# CMC_NIBP.net
KiCad netlist of a schematic drawn in EAGLE
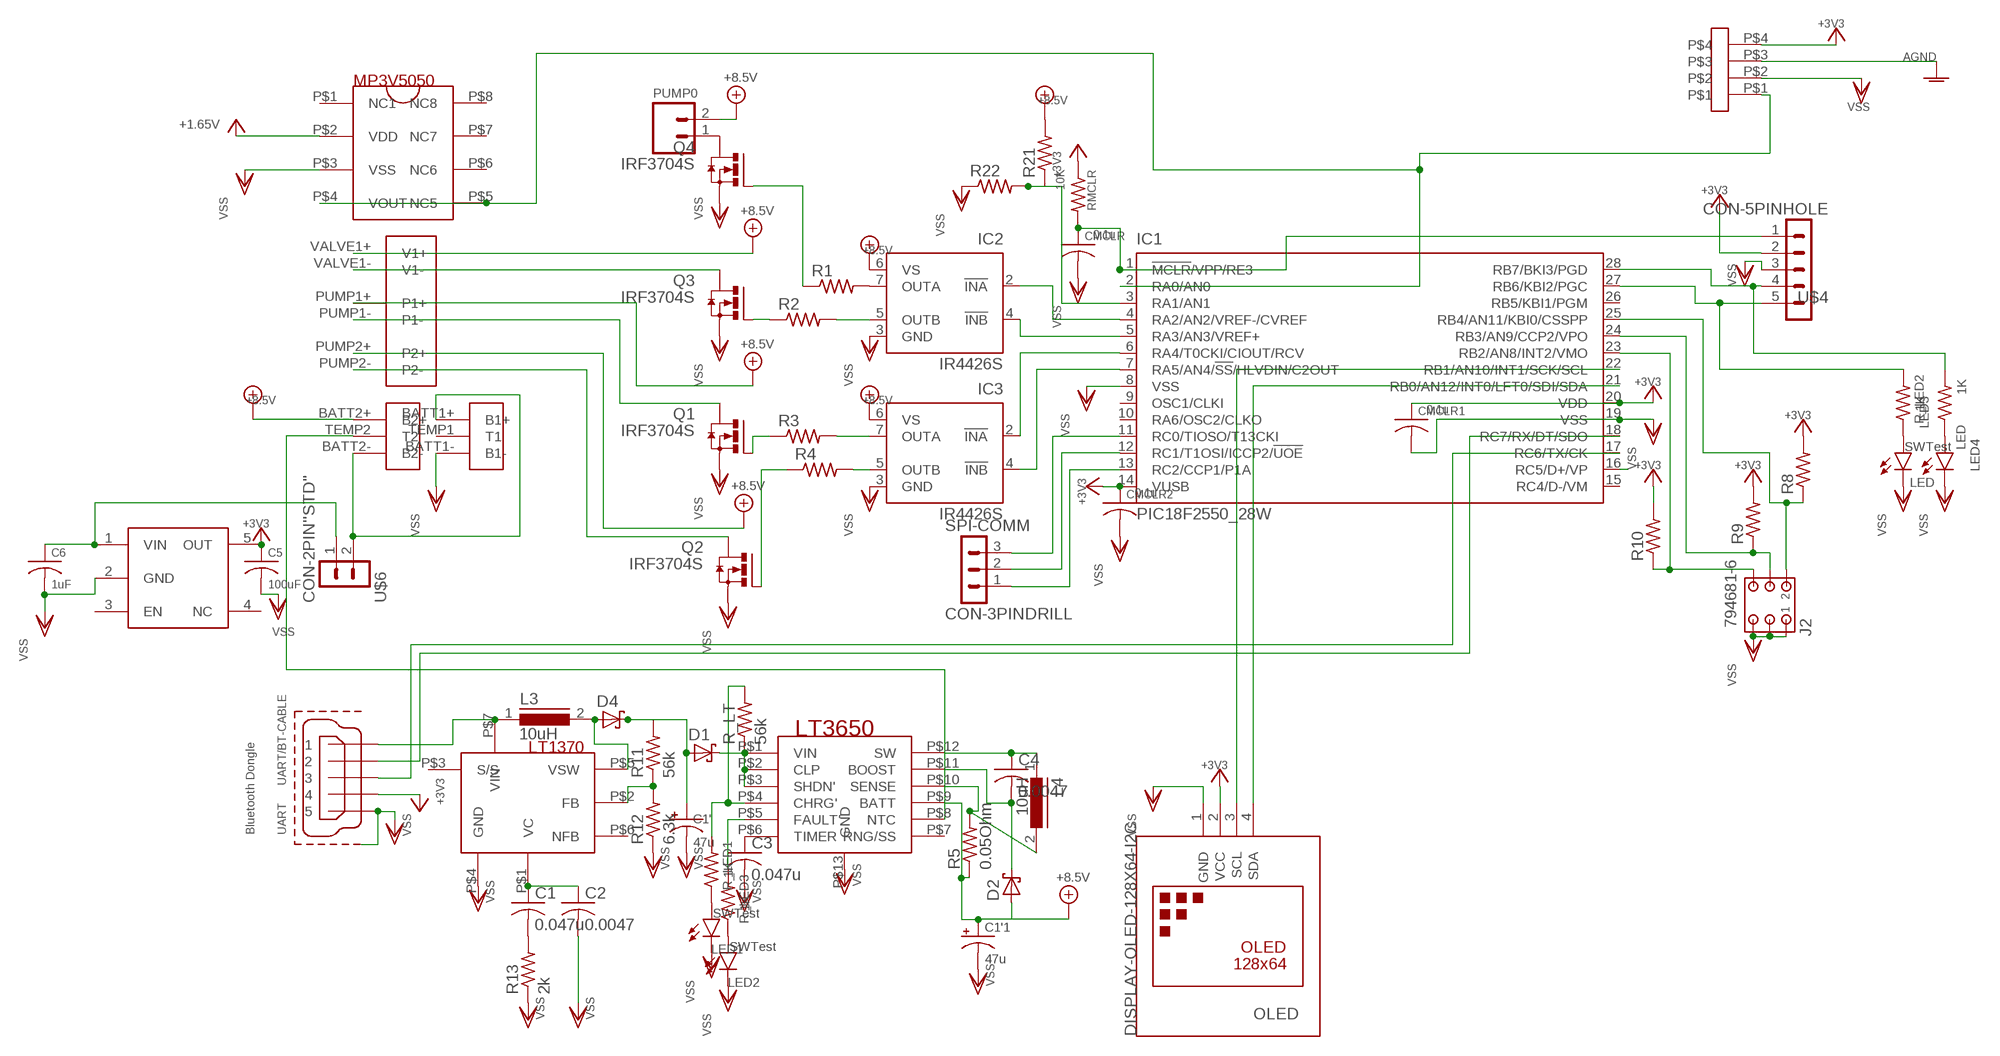
[diagram p0: schematic, sheet 1]

(export (version "E")
  (design (tool "Eeschema 10.0.6"))
  (components
    (comp (ref "C1")
      (value "0.047u")
      (footprint "eagle-import:C1206")
      (libsource (lib "eagle-import") (part "C-USC1206"))
    )
    (comp (ref "C1'")
      (value "47u")
      (footprint "eagle-import:E5-10,5")
      (libsource (lib "eagle-import") (part "CPOL-USE5-10.5"))
    )
    (comp (ref "C1'1")
      (value "47u")
      (footprint "eagle-import:E5-10,5")
      (libsource (lib "eagle-import") (part "CPOL-USE5-10.5"))
    )
    (comp (ref "C2")
      (value "0.0047")
      (footprint "eagle-import:C1206")
      (libsource (lib "eagle-import") (part "C-USC1206"))
    )
    (comp (ref "C3")
      (value "0.047u")
      (footprint "eagle-import:C1206")
      (libsource (lib "eagle-import") (part "C-USC1206"))
    )
    (comp (ref "C4")
      (value "0.0047")
      (footprint "eagle-import:C1206")
      (libsource (lib "eagle-import") (part "C-USC1206"))
    )
    (comp (ref "C5")
      (value "100uF")
      (footprint "eagle-import:C1210")
      (libsource (lib "eagle-import") (part "C-USC1210"))
    )
    (comp (ref "C6")
      (value "1uF")
      (footprint "eagle-import:C0603")
      (libsource (lib "eagle-import") (part "C-USC0603"))
    )
    (comp (ref "CMCLR")
      (value "0.1u")
      (footprint "eagle-import:C0603")
      (libsource (lib "eagle-import") (part "C-USC0603"))
    )
    (comp (ref "CMCLR1")
      (value "0.1u")
      (footprint "eagle-import:C0603")
      (libsource (lib "eagle-import") (part "C-USC0603"))
    )
    (comp (ref "CMCLR2")
      (value "0.1u")
      (footprint "eagle-import:C0603")
      (libsource (lib "eagle-import") (part "C-USC0603"))
    )
    (comp (ref "D1")
      (value "SCHOTTKY-DIODESMD")
      (footprint "eagle-import:SMB")
      (libsource (lib "eagle-import") (part "SCHOTTKY-DIODESMD"))
    )
    (comp (ref "D2")
      (value "SCHOTTKY-DIODESMD")
      (footprint "eagle-import:SMB")
      (libsource (lib "eagle-import") (part "SCHOTTKY-DIODESMD"))
    )
    (comp (ref "D4")
      (value "SCHOTTKY-DIODESMD")
      (footprint "eagle-import:SMB")
      (libsource (lib "eagle-import") (part "SCHOTTKY-DIODESMD"))
    )
    (comp (ref "IC-3.3VREG")
      (value "LDO-MIC5307")
      (footprint "eagle-import:SOT23-5")
      (libsource (lib "eagle-import") (part "LDO-MIC5307"))
    )
    (comp (ref "IC1")
      (value "PIC18F2550_28W")
      (footprint "eagle-import:SO28W")
      (fields (field (name "MF") "MICROCHIP") (field (name "MPN") "PIC18F2550-I/SO"))
      (libsource (lib "eagle-import") (part "PIC18F2_28W550"))
    )
    (comp (ref "IC2")
      (value "IR4426S")
      (footprint "eagle-import:SO08")
      (fields (field (name "MF") "INTERNATIONAL RECTIFIER(IR)"))
      (libsource (lib "eagle-import") (part "IR4426S"))
    )
    (comp (ref "IC3")
      (value "IR4426S")
      (footprint "eagle-import:SO08")
      (fields (field (name "MF") "INTERNATIONAL RECTIFIER(IR)"))
      (libsource (lib "eagle-import") (part "IR4426S"))
    )
    (comp (ref "J2")
      (value "794681-6")
      (footprint "eagle-import:794681-6")
      (libsource (lib "eagle-import") (part "794681-6"))
    )
    (comp (ref "L3")
      (value "10uH")
      (footprint "eagle-import:DR73")
      (libsource (lib "eagle-import") (part "DR73"))
    )
    (comp (ref "L4")
      (value "10uH")
      (footprint "eagle-import:DR73")
      (libsource (lib "eagle-import") (part "DR73"))
    )
    (comp (ref "LED")
      (value "SWTest")
      (footprint "eagle-import:LED3MM")
      (libsource (lib "eagle-import") (part "LED3MM"))
    )
    (comp (ref "LED1")
      (value "SWTest")
      (footprint "eagle-import:LED3MM")
      (libsource (lib "eagle-import") (part "LED3MM"))
    )
    (comp (ref "LED2")
      (value "SWTest")
      (footprint "eagle-import:LED3MM")
      (libsource (lib "eagle-import") (part "LED3MM"))
    )
    (comp (ref "LED3")
      (value "1K")
      (footprint "eagle-import:0204V")
      (libsource (lib "eagle-import") (part "R-US_0204/2V"))
    )
    (comp (ref "LED4")
      (value "LED")
      (footprint "eagle-import:LED3MM")
      (libsource (lib "eagle-import") (part "LED3MM"))
    )
    (comp (ref "OLED")
      (value "DISPLAY-OLED-128X64-I2C")
      (footprint "eagle-import:DISPLAY-OLED-128X64-I2C")
      (libsource (lib "eagle-import") (part "DISPLAY-OLED-128X64-I2C"))
    )
    (comp (ref "PUMP0")
      (value "Pump0")
      (footprint "eagle-import:02P")
      (libsource (lib "eagle-import") (part "M02"))
    )
    (comp (ref "Q1")
      (value "IRF3704S")
      (footprint "eagle-import:D2PACK")
      (libsource (lib "eagle-import") (part "IRF3704S"))
    )
    (comp (ref "Q2")
      (value "IRF3704S")
      (footprint "eagle-import:D2PACK")
      (libsource (lib "eagle-import") (part "IRF3704S"))
    )
    (comp (ref "Q3")
      (value "IRF3704S")
      (footprint "eagle-import:D2PACK")
      (libsource (lib "eagle-import") (part "IRF3704S"))
    )
    (comp (ref "Q4")
      (value "IRF3704S")
      (footprint "eagle-import:D2PACK")
      (libsource (lib "eagle-import") (part "IRF3704S"))
    )
    (comp (ref "R1")
      (value "R-US_M1206")
      (footprint "eagle-import:M1206")
      (libsource (lib "eagle-import") (part "R-US_M1206"))
    )
    (comp (ref "R2")
      (value "R-US_M1206")
      (footprint "eagle-import:M1206")
      (libsource (lib "eagle-import") (part "R-US_M1206"))
    )
    (comp (ref "R3")
      (value "R-US_M1206")
      (footprint "eagle-import:M1206")
      (libsource (lib "eagle-import") (part "R-US_M1206"))
    )
    (comp (ref "R4")
      (value "R-US_M1206")
      (footprint "eagle-import:M1206")
      (libsource (lib "eagle-import") (part "R-US_M1206"))
    )
    (comp (ref "R5")
      (value "0.05Ohm")
      (footprint "eagle-import:M1206")
      (libsource (lib "eagle-import") (part "R-US_M1206"))
    )
    (comp (ref "R8")
      (value "R-US_M1206")
      (footprint "eagle-import:M1206")
      (libsource (lib "eagle-import") (part "R-US_M1206"))
    )
    (comp (ref "R9")
      (value "R-US_M1206")
      (footprint "eagle-import:M1206")
      (libsource (lib "eagle-import") (part "R-US_M1206"))
    )
    (comp (ref "R10")
      (value "R-US_M1206")
      (footprint "eagle-import:M1206")
      (libsource (lib "eagle-import") (part "R-US_M1206"))
    )
    (comp (ref "R11")
      (value "56k")
      (footprint "eagle-import:M1206")
      (libsource (lib "eagle-import") (part "R-US_M1206"))
    )
    (comp (ref "R12")
      (value "6.3k")
      (footprint "eagle-import:M1206")
      (libsource (lib "eagle-import") (part "R-US_M1206"))
    )
    (comp (ref "R13")
      (value "2k")
      (footprint "eagle-import:M1206")
      (libsource (lib "eagle-import") (part "R-US_M1206"))
    )
    (comp (ref "R21")
      (value "R-US_M1206")
      (footprint "eagle-import:M1206")
      (libsource (lib "eagle-import") (part "R-US_M1206"))
    )
    (comp (ref "R22")
      (value "R-US_M1206")
      (footprint "eagle-import:M1206")
      (libsource (lib "eagle-import") (part "R-US_M1206"))
    )
    (comp (ref "RMCLR")
      (value "10K")
      (footprint "eagle-import:R0603")
      (libsource (lib "eagle-import") (part "R-US_R0603"))
    )
    (comp (ref "R_LED1")
      (value "1K")
      (footprint "eagle-import:0204V")
      (libsource (lib "eagle-import") (part "R-US_0204/2V"))
    )
    (comp (ref "R_LED2")
      (value "1K")
      (footprint "eagle-import:0204V")
      (libsource (lib "eagle-import") (part "R-US_0204/2V"))
    )
    (comp (ref "R_LED3")
      (value "1K")
      (footprint "eagle-import:0204V")
      (libsource (lib "eagle-import") (part "R-US_0204/2V"))
    )
    (comp (ref "R_LT")
      (value "56k")
      (footprint "eagle-import:M1206")
      (libsource (lib "eagle-import") (part "R-US_M1206"))
    )
    (comp (ref "SPI-COMM")
      (value "CON-3PINDRILL")
      (footprint "eagle-import:CON-3PIN")
      (libsource (lib "eagle-import") (part "CON-3PINDRILL"))
    )
    (comp (ref "U$1")
      (value "NIBP_PNEUMATICS")
      (footprint "eagle-import:NIBP_PNEUM")
      (libsource (lib "eagle-import") (part "NIBP_PNEUMATICS"))
    )
    (comp (ref "U$2")
      (value "LT1370")
      (footprint "eagle-import:DD-PACK-7LEAD")
      (libsource (lib "eagle-import") (part "LT1370"))
    )
    (comp (ref "U$3")
      (value "LT3650")
      (footprint "eagle-import:MSOP-12")
      (libsource (lib "eagle-import") (part "LT3650"))
    )
    (comp (ref "U$4")
      (value "CON-5PINHOLE")
      (footprint "eagle-import:CON-5PIN")
      (libsource (lib "eagle-import") (part "CON-5PINHOLE"))
    )
    (comp (ref "U$5")
      (value "CON-4PIN_SIL")
      (footprint "eagle-import:CONN-4PINSIL2")
      (libsource (lib "eagle-import") (part "CON-4PIN_SIL"))
    )
    (comp (ref "U$6")
      (value "CON-2PIN''STD\"")
      (footprint "eagle-import:CON-2PIN")
      (libsource (lib "eagle-import") (part "CON-2PIN''STD{dblquote}"))
    )
    (comp (ref "UART/BT-CABLE")
      (value "UART")
      (footprint "eagle-import:MICRO-USB1")
      (libsource (lib "eagle-import") (part "MICRO-USB1"))
    )
  )
  (nets
    (net (code "1") (name "+1.65V") (class "Default")
      (node (ref "C5") (pin "1") (pinfunction "1_1") (pintype "passive"))
      (node (ref "CMCLR1") (pin "1") (pinfunction "1_1") (pintype "passive"))
      (node (ref "CMCLR2") (pin "1") (pinfunction "1_1") (pintype "passive"))
      (node (ref "IC-3.3VREG") (pin "5") (pinfunction "OUT_5") (pintype "bidirectional"))
      (node (ref "IC1") (pin "14") (pinfunction "VUSB_14") (pintype "bidirectional"))
      (node (ref "IC1") (pin "20") (pinfunction "VDD_20") (pintype "power_in"))
      (node (ref "OLED") (pin "2") (pinfunction "VCC_2") (pintype "power_in"))
      (node (ref "R10") (pin "2") (pinfunction "2_2") (pintype "passive"))
      (node (ref "R8") (pin "2") (pinfunction "2_2") (pintype "passive"))
      (node (ref "R9") (pin "2") (pinfunction "2_2") (pintype "passive"))
      (node (ref "RMCLR") (pin "1") (pinfunction "1_1") (pintype "passive"))
      (node (ref "U$1") (pin "P$2") (pinfunction "VDD_P$2") (pintype "bidirectional"))
      (node (ref "U$4") (pin "2") (pinfunction "2_2") (pintype "passive"))
      (node (ref "U$5") (pin "P$4") (pinfunction "P$4_P$4") (pintype "bidirectional"))
      (node (ref "UART/BT-CABLE") (pin "4") (pinfunction "4_4") (pintype "input"))
    )
    (net (code "2") (name "+8.5V") (class "Default")
      (node (ref "C1'1") (pin "+") (pinfunction "+_+") (pintype "passive"))
      (node (ref "D2") (pin "A") (pinfunction "A_A") (pintype "passive"))
      (node (ref "IC2") (pin "6") (pinfunction "VS_6") (pintype "power_in"))
      (node (ref "IC3") (pin "6") (pinfunction "VS_6") (pintype "power_in"))
      (node (ref "PUMP0") (pin "2") (pinfunction "2_2") (pintype "passive"))
      (node (ref "R21") (pin "2") (pinfunction "2_2") (pintype "passive"))
      (node (ref "R5") (pin "1") (pinfunction "1_1") (pintype "passive"))
      (node (ref "U$1") (pin "BATT2+") (pinfunction "B2+_BATT2+") (pintype "bidirectional"))
      (node (ref "U$1") (pin "PUMP1+") (pinfunction "P1+_PUMP1+") (pintype "bidirectional"))
      (node (ref "U$1") (pin "PUMP2+") (pinfunction "P2+_PUMP2+") (pintype "bidirectional"))
      (node (ref "U$1") (pin "VALVE1+") (pinfunction "V1+_VALVE1+") (pintype "bidirectional"))
      (node (ref "U$3") (pin "P$9") (pinfunction "BATT_P$9") (pintype "bidirectional"))
    )
    (net (code "3") (name "AGND") (class "Default")
      (node (ref "U$5") (pin "P$3") (pinfunction "P$3_P$3") (pintype "bidirectional"))
    )
    (net (code "4") (name "Net-(C1'-Pad+)") (class "Default")
      (node (ref "C1'") (pin "+") (pinfunction "+_+") (pintype "passive"))
      (node (ref "D1") (pin "A") (pinfunction "A_A") (pintype "passive"))
      (node (ref "D4") (pin "C") (pinfunction "C_C") (pintype "passive"))
      (node (ref "R11") (pin "2") (pinfunction "2_2") (pintype "passive"))
    )
    (net (code "5") (name "Net-(C1-Pad2)") (class "Default")
      (node (ref "C1") (pin "2") (pinfunction "2_2") (pintype "passive"))
      (node (ref "R13") (pin "2") (pinfunction "2_2") (pintype "passive"))
    )
    (net (code "6") (name "Net-(IC-3.3VREG-VIN)") (class "Default")
      (node (ref "C6") (pin "1") (pinfunction "1_1") (pintype "passive"))
      (node (ref "IC-3.3VREG") (pin "1") (pinfunction "VIN_1") (pintype "bidirectional"))
      (node (ref "U$6") (pin "1") (pinfunction "1_1") (pintype "passive"))
    )
    (net (code "7") (name "Net-(IC1-RA0{slash}AN0)") (class "Default")
      (node (ref "IC1") (pin "2") (pinfunction "RA0/AN0_2") (pintype "bidirectional"))
      (node (ref "U$1") (pin "P$4") (pinfunction "VOUT_P$4") (pintype "bidirectional"))
      (node (ref "U$1") (pin "P$5") (pinfunction "NC5_P$5") (pintype "bidirectional"))
      (node (ref "U$5") (pin "P$1") (pinfunction "P$1_P$1") (pintype "bidirectional"))
    )
    (net (code "8") (name "Net-(IC1-RA1{slash}AN1)") (class "Default")
      (node (ref "IC1") (pin "3") (pinfunction "RA1/AN1_3") (pintype "bidirectional"))
      (node (ref "R21") (pin "1") (pinfunction "1_1") (pintype "passive"))
      (node (ref "R22") (pin "2") (pinfunction "2_2") (pintype "passive"))
    )
    (net (code "9") (name "Net-(IC1-RA2{slash}AN2{slash}VREF-{slash}CVREF)") (class "Default")
      (node (ref "IC1") (pin "4") (pinfunction "RA2/AN2/VREF-/CVREF_4") (pintype "bidirectional"))
      (node (ref "IC2") (pin "2") (pinfunction "~{INA}_2") (pintype "input"))
    )
    (net (code "10") (name "Net-(IC1-RA3{slash}AN3{slash}VREF+)") (class "Default")
      (node (ref "IC1") (pin "5") (pinfunction "RA3/AN3/VREF+_5") (pintype "bidirectional"))
      (node (ref "IC2") (pin "4") (pinfunction "~{INB}_4") (pintype "input"))
    )
    (net (code "11") (name "Net-(IC1-RA4{slash}T0CKI{slash}CIOUT{slash}RCV)") (class "Default")
      (node (ref "IC1") (pin "6") (pinfunction "RA4/T0CKI/CIOUT/RCV_6") (pintype "bidirectional"))
      (node (ref "IC3") (pin "2") (pinfunction "~{INA}_2") (pintype "input"))
    )
    (net (code "12") (name "Net-(IC1-RA5{slash}AN4{slash}~{SS}{slash}HLVDIN{slash}C2OUT)") (class "Default")
      (node (ref "IC1") (pin "7") (pinfunction "RA5/AN4/~{SS}/HLVDIN/C2OUT_7") (pintype "bidirectional"))
      (node (ref "IC3") (pin "4") (pinfunction "~{INB}_4") (pintype "input"))
    )
    (net (code "13") (name "Net-(IC1-RB0{slash}AN12{slash}INT0{slash}LFT0{slash}SDI{slash}SDA)") (class "Default")
      (node (ref "IC1") (pin "21") (pinfunction "RB0/AN12/INT0/LFT0/SDI/SDA_21") (pintype "bidirectional"))
      (node (ref "OLED") (pin "4") (pinfunction "SDA_4") (pintype "bidirectional"))
    )
    (net (code "14") (name "Net-(IC1-RB1{slash}AN10{slash}INT1{slash}SCK{slash}SCL)") (class "Default")
      (node (ref "IC1") (pin "22") (pinfunction "RB1/AN10/INT1/SCK/SCL_22") (pintype "bidirectional"))
      (node (ref "OLED") (pin "3") (pinfunction "SCL_3") (pintype "bidirectional"))
    )
    (net (code "15") (name "Net-(IC1-RB2{slash}AN8{slash}INT2{slash}VMO)") (class "Default")
      (node (ref "IC1") (pin "23") (pinfunction "RB2/AN8/INT2/VMO_23") (pintype "bidirectional"))
      (node (ref "J2") (pin "6") (pinfunction "6_6") (pintype "passive"))
      (node (ref "R10") (pin "1") (pinfunction "1_1") (pintype "passive"))
    )
    (net (code "16") (name "Net-(IC1-RB3{slash}AN9{slash}CCP2{slash}VPO)") (class "Default")
      (node (ref "IC1") (pin "24") (pinfunction "RB3/AN9/CCP2/VPO_24") (pintype "bidirectional"))
      (node (ref "J2") (pin "4") (pinfunction "4_4") (pintype "passive"))
      (node (ref "R9") (pin "1") (pinfunction "1_1") (pintype "passive"))
    )
    (net (code "17") (name "Net-(IC1-RB4{slash}AN11{slash}KBI0{slash}CSSPP)") (class "Default")
      (node (ref "IC1") (pin "25") (pinfunction "RB4/AN11/KBI0/CSSPP_25") (pintype "bidirectional"))
      (node (ref "J2") (pin "2") (pinfunction "2_2") (pintype "passive"))
      (node (ref "R8") (pin "1") (pinfunction "1_1") (pintype "passive"))
    )
    (net (code "18") (name "Net-(IC1-RB6{slash}KBI2{slash}PGC)") (class "Default")
      (node (ref "IC1") (pin "27") (pinfunction "RB6/KBI2/PGC_27") (pintype "bidirectional"))
      (node (ref "R_LED2") (pin "2") (pinfunction "2_2") (pintype "passive"))
      (node (ref "U$4") (pin "5") (pinfunction "5_5") (pintype "passive"))
    )
    (net (code "19") (name "Net-(IC1-RB7{slash}BKI3{slash}PGD)") (class "Default")
      (node (ref "IC1") (pin "28") (pinfunction "RB7/BKI3/PGD_28") (pintype "bidirectional"))
      (node (ref "LED3") (pin "2") (pinfunction "2_2") (pintype "passive"))
      (node (ref "U$4") (pin "4") (pinfunction "4_4") (pintype "passive"))
    )
    (net (code "20") (name "Net-(IC1-RC0{slash}TIOSO{slash}T13CKI)") (class "Default")
      (node (ref "IC1") (pin "11") (pinfunction "RC0/TIOSO/T13CKI_11") (pintype "bidirectional"))
      (node (ref "SPI-COMM") (pin "3") (pinfunction "3_3") (pintype "passive"))
    )
    (net (code "21") (name "Net-(IC1-RC1{slash}T1OSI{slash}ICCP2{slash}~{UOE})") (class "Default")
      (node (ref "IC1") (pin "12") (pinfunction "RC1/T1OSI/ICCP2/~{UOE}_12") (pintype "bidirectional"))
      (node (ref "SPI-COMM") (pin "2") (pinfunction "2_2") (pintype "passive"))
    )
    (net (code "22") (name "Net-(IC1-RC2{slash}CCP1{slash}P1A)") (class "Default")
      (node (ref "IC1") (pin "13") (pinfunction "RC2/CCP1/P1A_13") (pintype "bidirectional"))
      (node (ref "SPI-COMM") (pin "1") (pinfunction "1_1") (pintype "passive"))
    )
    (net (code "23") (name "Net-(IC1-RC6{slash}TX{slash}CK)") (class "Default")
      (node (ref "IC1") (pin "17") (pinfunction "RC6/TX/CK_17") (pintype "bidirectional"))
      (node (ref "UART/BT-CABLE") (pin "3") (pinfunction "3_3") (pintype "input"))
    )
    (net (code "24") (name "Net-(IC1-RC7{slash}RX{slash}DT{slash}SDO)") (class "Default")
      (node (ref "IC1") (pin "18") (pinfunction "RC7/RX/DT/SDO_18") (pintype "bidirectional"))
      (node (ref "UART/BT-CABLE") (pin "2") (pinfunction "2_2") (pintype "input"))
    )
    (net (code "25") (name "Net-(IC1-~{MCLR}{slash}VPP{slash}RE3)") (class "Default")
      (node (ref "CMCLR") (pin "1") (pinfunction "1_1") (pintype "passive"))
      (node (ref "IC1") (pin "1") (pinfunction "~{MCLR}/VPP/RE3_1") (pintype "input"))
      (node (ref "RMCLR") (pin "2") (pinfunction "2_2") (pintype "passive"))
      (node (ref "U$4") (pin "1") (pinfunction "1_1") (pintype "passive"))
    )
    (net (code "26") (name "Net-(IC2-OUTA)") (class "Default")
      (node (ref "IC2") (pin "7") (pinfunction "OUTA_7") (pintype "output"))
      (node (ref "R1") (pin "2") (pinfunction "2_2") (pintype "passive"))
    )
    (net (code "27") (name "Net-(IC2-OUTB)") (class "Default")
      (node (ref "IC2") (pin "5") (pinfunction "OUTB_5") (pintype "output"))
      (node (ref "R2") (pin "2") (pinfunction "2_2") (pintype "passive"))
    )
    (net (code "28") (name "Net-(IC3-OUTA)") (class "Default")
      (node (ref "IC3") (pin "7") (pinfunction "OUTA_7") (pintype "output"))
      (node (ref "R3") (pin "2") (pinfunction "2_2") (pintype "passive"))
    )
    (net (code "29") (name "Net-(IC3-OUTB)") (class "Default")
      (node (ref "IC3") (pin "5") (pinfunction "OUTB_5") (pintype "output"))
      (node (ref "R4") (pin "2") (pinfunction "2_2") (pintype "passive"))
    )
    (net (code "30") (name "Net-(LED-PadA)") (class "Default")
      (node (ref "LED") (pin "A") (pinfunction "A_A") (pintype "passive"))
      (node (ref "R_LED2") (pin "1") (pinfunction "1_1") (pintype "passive"))
    )
    (net (code "31") (name "Net-(LED1-PadA)") (class "Default")
      (node (ref "LED1") (pin "A") (pinfunction "A_A") (pintype "passive"))
      (node (ref "R_LED1") (pin "1") (pinfunction "1_1") (pintype "passive"))
    )
    (net (code "32") (name "Net-(LED2-PadA)") (class "Default")
      (node (ref "LED2") (pin "A") (pinfunction "A_A") (pintype "passive"))
      (node (ref "R_LED3") (pin "1") (pinfunction "1_1") (pintype "passive"))
    )
    (net (code "33") (name "Net-(LED3-Pad1)") (class "Default")
      (node (ref "LED3") (pin "1") (pinfunction "1_1") (pintype "passive"))
      (node (ref "LED4") (pin "A") (pinfunction "A_A") (pintype "passive"))
    )
    (net (code "34") (name "Net-(Q1-D)") (class "Default")
      (node (ref "Q1") (pin "2") (pinfunction "D_2") (pintype "passive"))
      (node (ref "U$1") (pin "PUMP1-") (pinfunction "P1-_PUMP1-") (pintype "bidirectional"))
    )
    (net (code "35") (name "Net-(Q1-G)") (class "Default")
      (node (ref "Q1") (pin "1") (pinfunction "G_1") (pintype "passive"))
      (node (ref "R3") (pin "1") (pinfunction "1_1") (pintype "passive"))
    )
    (net (code "36") (name "Net-(Q2-D)") (class "Default")
      (node (ref "Q2") (pin "2") (pinfunction "D_2") (pintype "passive"))
      (node (ref "U$1") (pin "PUMP2-") (pinfunction "P2-_PUMP2-") (pintype "bidirectional"))
    )
    (net (code "37") (name "Net-(Q2-G)") (class "Default")
      (node (ref "Q2") (pin "1") (pinfunction "G_1") (pintype "passive"))
      (node (ref "R4") (pin "1") (pinfunction "1_1") (pintype "passive"))
    )
    (net (code "38") (name "Net-(Q3-D)") (class "Default")
      (node (ref "Q3") (pin "2") (pinfunction "D_2") (pintype "passive"))
      (node (ref "U$1") (pin "VALVE1-") (pinfunction "V1-_VALVE1-") (pintype "bidirectional"))
    )
    (net (code "39") (name "Net-(Q3-G)") (class "Default")
      (node (ref "Q3") (pin "1") (pinfunction "G_1") (pintype "passive"))
      (node (ref "R2") (pin "1") (pinfunction "1_1") (pintype "passive"))
    )
    (net (code "40") (name "Net-(Q4-D)") (class "Default")
      (node (ref "PUMP0") (pin "1") (pinfunction "1_1") (pintype "passive"))
      (node (ref "Q4") (pin "2") (pinfunction "D_2") (pintype "passive"))
    )
    (net (code "41") (name "Net-(Q4-G)") (class "Default")
      (node (ref "Q4") (pin "1") (pinfunction "G_1") (pintype "passive"))
      (node (ref "R1") (pin "1") (pinfunction "1_1") (pintype "passive"))
    )
    (net (code "42") (name "Net-(U$1-B1+)") (class "Default")
      (node (ref "U$1") (pin "BATT1+") (pinfunction "B1+_BATT1+") (pintype "bidirectional"))
      (node (ref "U$1") (pin "BATT2-") (pinfunction "B2-_BATT2-") (pintype "bidirectional"))
      (node (ref "U$6") (pin "2") (pinfunction "2_2") (pintype "passive"))
    )
    (net (code "43") (name "Net-(U$1-T2)") (class "Default")
      (node (ref "U$1") (pin "TEMP2") (pinfunction "T2_TEMP2") (pintype "bidirectional"))
      (node (ref "U$3") (pin "P$8") (pinfunction "NTC_P$8") (pintype "bidirectional"))
    )
    (net (code "44") (name "Net-(U$2-FB)") (class "Default")
      (node (ref "R11") (pin "1") (pinfunction "1_1") (pintype "passive"))
      (node (ref "R12") (pin "2") (pinfunction "2_2") (pintype "passive"))
      (node (ref "U$2") (pin "P$2") (pinfunction "FB_P$2") (pintype "bidirectional"))
    )
    (net (code "45") (name "Net-(U$2-VC)") (class "Default")
      (node (ref "C1") (pin "1") (pinfunction "1_1") (pintype "passive"))
      (node (ref "C2") (pin "1") (pinfunction "1_1") (pintype "passive"))
      (node (ref "U$2") (pin "P$1") (pinfunction "VC_P$1") (pintype "bidirectional"))
    )
    (net (code "46") (name "Net-(U$2-VIN)") (class "Default")
      (node (ref "L3") (pin "1") (pinfunction "1_1") (pintype "passive"))
      (node (ref "U$2") (pin "P$7") (pinfunction "VIN_P$7") (pintype "bidirectional"))
      (node (ref "UART/BT-CABLE") (pin "1") (pinfunction "1_1") (pintype "input"))
    )
    (net (code "47") (name "Net-(U$2-VSW)") (class "Default")
      (node (ref "D4") (pin "A") (pinfunction "A_A") (pintype "passive"))
      (node (ref "L3") (pin "2") (pinfunction "2_2") (pintype "passive"))
      (node (ref "U$2") (pin "P$5") (pinfunction "VSW_P$5") (pintype "bidirectional"))
    )
    (net (code "48") (name "Net-(U$3-BOOST)") (class "Default")
      (node (ref "C4") (pin "2") (pinfunction "2_2") (pintype "passive"))
      (node (ref "D2") (pin "C") (pinfunction "C_C") (pintype "passive"))
      (node (ref "U$3") (pin "P$11") (pinfunction "BOOST_P$11") (pintype "bidirectional"))
    )
    (net (code "49") (name "Net-(U$3-CHRG')") (class "Default")
      (node (ref "R_LED1") (pin "2") (pinfunction "2_2") (pintype "passive"))
      (node (ref "R_LT") (pin "2") (pinfunction "2_2") (pintype "passive"))
      (node (ref "U$3") (pin "P$4") (pinfunction "CHRG'_P$4") (pintype "bidirectional"))
    )
    (net (code "50") (name "Net-(U$3-CLP)") (class "Default")
      (node (ref "D1") (pin "C") (pinfunction "C_C") (pintype "passive"))
      (node (ref "R_LT") (pin "1") (pinfunction "1_1") (pintype "passive"))
      (node (ref "U$3") (pin "P$1") (pinfunction "VIN_P$1") (pintype "bidirectional"))
      (node (ref "U$3") (pin "P$2") (pinfunction "CLP_P$2") (pintype "bidirectional"))
      (node (ref "U$3") (pin "P$3") (pinfunction "SHDN'_P$3") (pintype "bidirectional"))
    )
    (net (code "51") (name "Net-(U$3-FAULT')") (class "Default")
      (node (ref "R_LED3") (pin "2") (pinfunction "2_2") (pintype "passive"))
      (node (ref "U$3") (pin "P$5") (pinfunction "FAULT'_P$5") (pintype "bidirectional"))
    )
    (net (code "52") (name "Net-(U$3-SENSE)") (class "Default")
      (node (ref "L4") (pin "2") (pinfunction "2_2") (pintype "passive"))
      (node (ref "R5") (pin "2") (pinfunction "2_2") (pintype "passive"))
      (node (ref "U$3") (pin "P$10") (pinfunction "SENSE_P$10") (pintype "bidirectional"))
    )
    (net (code "53") (name "Net-(U$3-SW)") (class "Default")
      (node (ref "C4") (pin "1") (pinfunction "1_1") (pintype "passive"))
      (node (ref "L4") (pin "1") (pinfunction "1_1") (pintype "passive"))
      (node (ref "U$3") (pin "P$12") (pinfunction "SW_P$12") (pintype "bidirectional"))
    )
    (net (code "54") (name "Net-(U$3-TIMER)") (class "Default")
      (node (ref "C3") (pin "1") (pinfunction "1_1") (pintype "passive"))
      (node (ref "U$3") (pin "P$6") (pinfunction "TIMER_P$6") (pintype "bidirectional"))
    )
    (net (code "55") (name "VSS") (class "Default")
      (node (ref "C1'") (pin "-") (pinfunction "-_-") (pintype "passive"))
      (node (ref "C1'1") (pin "-") (pinfunction "-_-") (pintype "passive"))
      (node (ref "C2") (pin "2") (pinfunction "2_2") (pintype "passive"))
      (node (ref "C3") (pin "2") (pinfunction "2_2") (pintype "passive"))
      (node (ref "C5") (pin "2") (pinfunction "2_2") (pintype "passive"))
      (node (ref "C6") (pin "2") (pinfunction "2_2") (pintype "passive"))
      (node (ref "CMCLR") (pin "2") (pinfunction "2_2") (pintype "passive"))
      (node (ref "CMCLR1") (pin "2") (pinfunction "2_2") (pintype "passive"))
      (node (ref "CMCLR2") (pin "2") (pinfunction "2_2") (pintype "passive"))
      (node (ref "IC-3.3VREG") (pin "2") (pinfunction "GND_2") (pintype "bidirectional"))
      (node (ref "IC1") (pin "19") (pinfunction "VSS_19") (pintype "power_in"))
      (node (ref "IC1") (pin "8") (pinfunction "VSS_8") (pintype "power_in"))
      (node (ref "IC2") (pin "3") (pinfunction "GND_3") (pintype "power_in"))
      (node (ref "IC3") (pin "3") (pinfunction "GND_3") (pintype "power_in"))
      (node (ref "J2") (pin "1") (pinfunction "1_1") (pintype "passive"))
      (node (ref "J2") (pin "3") (pinfunction "3_3") (pintype "passive"))
      (node (ref "J2") (pin "5") (pinfunction "5_5") (pintype "passive"))
      (node (ref "LED") (pin "K") (pinfunction "C_K") (pintype "passive"))
      (node (ref "LED1") (pin "K") (pinfunction "C_K") (pintype "passive"))
      (node (ref "LED2") (pin "K") (pinfunction "C_K") (pintype "passive"))
      (node (ref "LED4") (pin "K") (pinfunction "C_K") (pintype "passive"))
      (node (ref "OLED") (pin "1") (pinfunction "GND_1") (pintype "power_in"))
      (node (ref "Q1") (pin "3") (pinfunction "S_3") (pintype "passive"))
      (node (ref "Q2") (pin "3") (pinfunction "S_3") (pintype "passive"))
      (node (ref "Q3") (pin "3") (pinfunction "S_3") (pintype "passive"))
      (node (ref "Q4") (pin "3") (pinfunction "S_3") (pintype "passive"))
      (node (ref "R12") (pin "1") (pinfunction "1_1") (pintype "passive"))
      (node (ref "R13") (pin "1") (pinfunction "1_1") (pintype "passive"))
      (node (ref "R22") (pin "1") (pinfunction "1_1") (pintype "passive"))
      (node (ref "U$1") (pin "BATT1-") (pinfunction "B1-_BATT1-") (pintype "bidirectional"))
      (node (ref "U$1") (pin "P$3") (pinfunction "VSS_P$3") (pintype "bidirectional"))
      (node (ref "U$2") (pin "P$4") (pinfunction "GND_P$4") (pintype "bidirectional"))
      (node (ref "U$3") (pin "P$13") (pinfunction "GND_P$13") (pintype "bidirectional"))
      (node (ref "U$4") (pin "3") (pinfunction "3_3") (pintype "passive"))
      (node (ref "U$5") (pin "P$2") (pinfunction "P$2_P$2") (pintype "bidirectional"))
      (node (ref "UART/BT-CABLE") (pin "5") (pinfunction "5_5") (pintype "input"))
    )
    (net (code "56") (name "unconnected-(IC-3.3VREG-EN-Pad3)") (class "Default")
      (node (ref "IC-3.3VREG") (pin "3") (pinfunction "EN_3") (pintype "bidirectional"))
    )
    (net (code "57") (name "unconnected-(IC-3.3VREG-NC-Pad4)") (class "Default")
      (node (ref "IC-3.3VREG") (pin "4") (pinfunction "NC_4") (pintype "bidirectional"))
    )
    (net (code "58") (name "unconnected-(IC1-OSC1{slash}CLKI-Pad9)") (class "Default")
      (node (ref "IC1") (pin "9") (pinfunction "OSC1/CLKI_9") (pintype "input"))
    )
    (net (code "59") (name "unconnected-(IC1-RA6{slash}OSC2{slash}CLKO-Pad10)") (class "Default")
      (node (ref "IC1") (pin "10") (pinfunction "RA6/OSC2/CLKO_10") (pintype "output"))
    )
    (net (code "60") (name "unconnected-(IC1-RB5{slash}KBI1{slash}PGM-Pad26)") (class "Default")
      (node (ref "IC1") (pin "26") (pinfunction "RB5/KBI1/PGM_26") (pintype "bidirectional"))
    )
    (net (code "61") (name "unconnected-(IC1-RC4{slash}D-{slash}VM-Pad15)") (class "Default")
      (node (ref "IC1") (pin "15") (pinfunction "RC4/D-/VM_15") (pintype "bidirectional"))
    )
    (net (code "62") (name "unconnected-(IC1-RC5{slash}D+{slash}VP-Pad16)") (class "Default")
      (node (ref "IC1") (pin "16") (pinfunction "RC5/D+/VP_16") (pintype "bidirectional"))
    )
    (net (code "63") (name "unconnected-(U$1-NC1-PadP$1)") (class "Default")
      (node (ref "U$1") (pin "P$1") (pinfunction "NC1_P$1") (pintype "bidirectional"))
    )
    (net (code "64") (name "unconnected-(U$1-NC6-PadP$6)") (class "Default")
      (node (ref "U$1") (pin "P$6") (pinfunction "NC6_P$6") (pintype "bidirectional"))
    )
    (net (code "65") (name "unconnected-(U$1-NC7-PadP$7)") (class "Default")
      (node (ref "U$1") (pin "P$7") (pinfunction "NC7_P$7") (pintype "bidirectional"))
    )
    (net (code "66") (name "unconnected-(U$1-NC8-PadP$8)") (class "Default")
      (node (ref "U$1") (pin "P$8") (pinfunction "NC8_P$8") (pintype "bidirectional"))
    )
    (net (code "67") (name "unconnected-(U$1-T1-PadTEMP1)") (class "Default")
      (node (ref "U$1") (pin "TEMP1") (pinfunction "T1_TEMP1") (pintype "bidirectional"))
    )
    (net (code "68") (name "unconnected-(U$2-NFB-PadP$6)") (class "Default")
      (node (ref "U$2") (pin "P$6") (pinfunction "NFB_P$6") (pintype "bidirectional"))
    )
    (net (code "69") (name "unconnected-(U$2-S{slash}S-PadP$3)") (class "Default")
      (node (ref "U$2") (pin "P$3") (pinfunction "S/S_P$3") (pintype "bidirectional"))
    )
    (net (code "70") (name "unconnected-(U$3-RNG{slash}SS-PadP$7)") (class "Default")
      (node (ref "U$3") (pin "P$7") (pinfunction "RNG/SS_P$7") (pintype "bidirectional"))
    )
  )
)
